# breakout_HTSSOP.net
KiCad netlist of a schematic drawn in Altium Designer
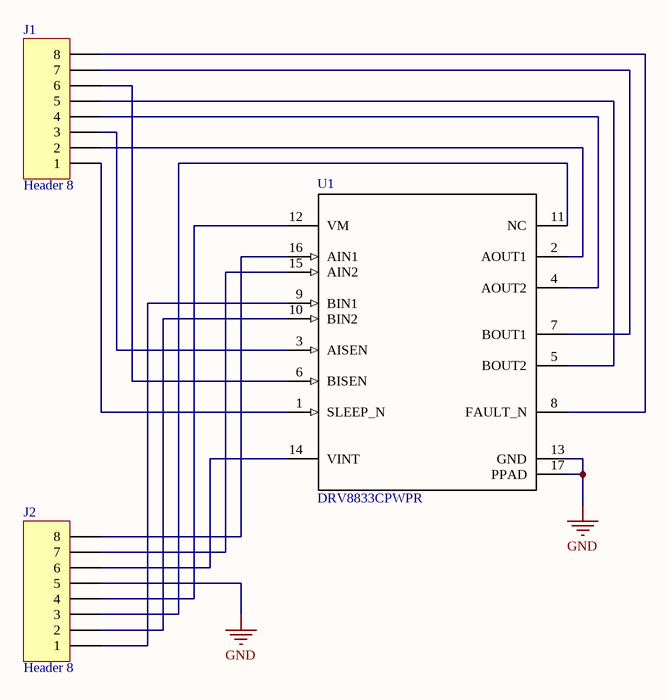
[diagram p0: breakout_HTSSOP.SchDoc]

(export (version "E")
  (design (tool "Eeschema 10.0.6"))
  (components
    (comp (ref "J1")
      (value "Header 8")
      (footprint "HDR1X8")
      (description "Header, 8-Pin")
      (fields (field (name "PUBLISHER") "Altium Limited"))
      (libsource (lib "Miscellaneous Connectors") (part "Header 8"))
    )
    (comp (ref "J2")
      (value "Header 8")
      (footprint "HDR1X8")
      (description "Header, 8-Pin")
      (fields (field (name "PUBLISHER") "Altium Limited"))
      (libsource (lib "Miscellaneous Connectors") (part "Header 8"))
    )
    (comp (ref "U1")
      (value "DRV8833CPWPR")
      (footprint "htssop16")
      (description "Imported")
      (fields
        (field (name "ALTERNATE PARTNUMBER") "DRV8833CPWP")
        (field (name "MANUFACTURER") "Texas Instruments")
      )
      (libsource (lib "DRV8833C_HTSSOP") (part "DRV8833CPWPR"))
    )
  )
  (nets
    (net (code "1") (name "GND") (class "Default")
      (node (ref "J2") (pin "5") (pinfunction "5_5") (pintype "passive"))
      (node (ref "U1") (pin "13") (pinfunction "GND_13") (pintype "power_in"))
      (node (ref "U1") (pin "17") (pinfunction "PPAD_17") (pintype "power_in"))
    )
    (net (code "2") (name "Net-(U1-AIN1)") (class "Default")
      (node (ref "J2") (pin "8") (pinfunction "8_8") (pintype "passive"))
      (node (ref "U1") (pin "16") (pinfunction "AIN1_16") (pintype "input"))
    )
    (net (code "3") (name "Net-(U1-AIN2)") (class "Default")
      (node (ref "J2") (pin "7") (pinfunction "7_7") (pintype "passive"))
      (node (ref "U1") (pin "15") (pinfunction "AIN2_15") (pintype "input"))
    )
    (net (code "4") (name "Net-(U1-AISEN)") (class "Default")
      (node (ref "J1") (pin "3") (pinfunction "3_3") (pintype "passive"))
      (node (ref "U1") (pin "3") (pinfunction "AISEN_3") (pintype "input"))
    )
    (net (code "5") (name "Net-(U1-AOUT1)") (class "Default")
      (node (ref "J1") (pin "2") (pinfunction "2_2") (pintype "passive"))
      (node (ref "U1") (pin "2") (pinfunction "AOUT1_2") (pintype "tri_state"))
    )
    (net (code "6") (name "Net-(U1-AOUT2)") (class "Default")
      (node (ref "J1") (pin "4") (pinfunction "4_4") (pintype "passive"))
      (node (ref "U1") (pin "4") (pinfunction "AOUT2_4") (pintype "tri_state"))
    )
    (net (code "7") (name "Net-(U1-BIN1)") (class "Default")
      (node (ref "J2") (pin "1") (pinfunction "1_1") (pintype "passive"))
      (node (ref "U1") (pin "9") (pinfunction "BIN1_9") (pintype "input"))
    )
    (net (code "8") (name "Net-(U1-BIN2)") (class "Default")
      (node (ref "J2") (pin "2") (pinfunction "2_2") (pintype "passive"))
      (node (ref "U1") (pin "10") (pinfunction "BIN2_10") (pintype "input"))
    )
    (net (code "9") (name "Net-(U1-BISEN)") (class "Default")
      (node (ref "J1") (pin "6") (pinfunction "6_6") (pintype "passive"))
      (node (ref "U1") (pin "6") (pinfunction "BISEN_6") (pintype "input"))
    )
    (net (code "10") (name "Net-(U1-BOUT1)") (class "Default")
      (node (ref "J1") (pin "7") (pinfunction "7_7") (pintype "passive"))
      (node (ref "U1") (pin "7") (pinfunction "BOUT1_7") (pintype "tri_state"))
    )
    (net (code "11") (name "Net-(U1-BOUT2)") (class "Default")
      (node (ref "J1") (pin "5") (pinfunction "5_5") (pintype "passive"))
      (node (ref "U1") (pin "5") (pinfunction "BOUT2_5") (pintype "tri_state"))
    )
    (net (code "12") (name "Net-(U1-FAULT_N)") (class "Default")
      (node (ref "J1") (pin "8") (pinfunction "8_8") (pintype "passive"))
      (node (ref "U1") (pin "8") (pinfunction "FAULT_N_8") (pintype "open_collector"))
    )
    (net (code "13") (name "Net-(U1-NC)") (class "Default")
      (node (ref "J2") (pin "3") (pinfunction "3_3") (pintype "passive"))
      (node (ref "U1") (pin "11") (pinfunction "NC_11") (pintype "passive"))
    )
    (net (code "14") (name "Net-(U1-SLEEP_N)") (class "Default")
      (node (ref "J1") (pin "1") (pinfunction "1_1") (pintype "passive"))
      (node (ref "U1") (pin "1") (pinfunction "SLEEP_N_1") (pintype "input"))
    )
    (net (code "15") (name "Net-(U1-VINT)") (class "Default")
      (node (ref "J2") (pin "6") (pinfunction "6_6") (pintype "passive"))
      (node (ref "U1") (pin "14") (pinfunction "VINT_14") (pintype "passive"))
    )
    (net (code "16") (name "Net-(U1-VM)") (class "Default")
      (node (ref "J2") (pin "4") (pinfunction "4_4") (pintype "passive"))
      (node (ref "U1") (pin "12") (pinfunction "VM_12") (pintype "power_in"))
    )
  )
)
